# LED_rev3.net
KiCad netlist of a schematic drawn in EAGLE
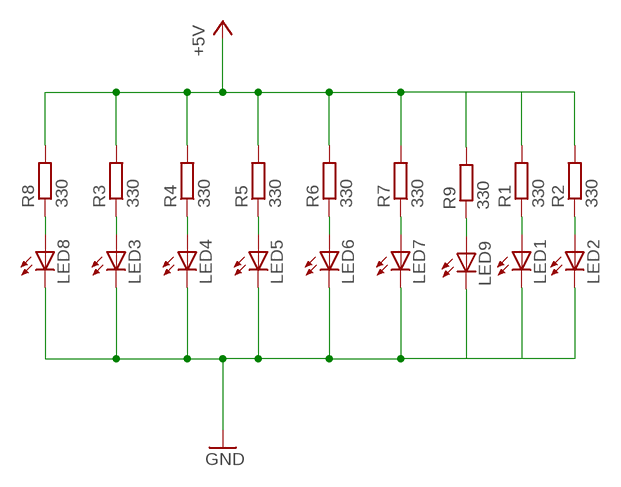
[diagram p0: schematic, sheet 1]

(export (version "E")
  (design (tool "Eeschema 10.0.6"))
  (components
    (comp (ref "LED1")
      (value "LEDCHIPLED_0603")
      (footprint "eagle-import:CHIPLED_0603")
      (libsource (lib "eagle-import") (part "LEDCHIPLED_0603"))
    )
    (comp (ref "LED2")
      (value "LEDCHIPLED_0603")
      (footprint "eagle-import:CHIPLED_0603")
      (libsource (lib "eagle-import") (part "LEDCHIPLED_0603"))
    )
    (comp (ref "LED3")
      (value "LEDCHIPLED_0603")
      (footprint "eagle-import:CHIPLED_0603")
      (libsource (lib "eagle-import") (part "LEDCHIPLED_0603"))
    )
    (comp (ref "LED4")
      (value "LEDCHIPLED_0603")
      (footprint "eagle-import:CHIPLED_0603")
      (libsource (lib "eagle-import") (part "LEDCHIPLED_0603"))
    )
    (comp (ref "LED5")
      (value "LEDCHIPLED_0603")
      (footprint "eagle-import:CHIPLED_0603")
      (libsource (lib "eagle-import") (part "LEDCHIPLED_0603"))
    )
    (comp (ref "LED6")
      (value "LEDCHIPLED_0603")
      (footprint "eagle-import:CHIPLED_0603")
      (libsource (lib "eagle-import") (part "LEDCHIPLED_0603"))
    )
    (comp (ref "LED7")
      (value "LEDCHIPLED_0603")
      (footprint "eagle-import:CHIPLED_0603")
      (libsource (lib "eagle-import") (part "LEDCHIPLED_0603"))
    )
    (comp (ref "LED8")
      (value "LEDCHIPLED_0603")
      (footprint "eagle-import:CHIPLED_0603")
      (libsource (lib "eagle-import") (part "LEDCHIPLED_0603"))
    )
    (comp (ref "LED9")
      (value "LEDCHIPLED_0603")
      (footprint "eagle-import:CHIPLED_0603")
      (libsource (lib "eagle-import") (part "LEDCHIPLED_0603"))
    )
    (comp (ref "R1")
      (value "330")
      (footprint "eagle-import:R0603")
      (libsource (lib "eagle-import") (part "R-EU_R0603"))
    )
    (comp (ref "R2")
      (value "330")
      (footprint "eagle-import:R0603")
      (libsource (lib "eagle-import") (part "R-EU_R0603"))
    )
    (comp (ref "R3")
      (value "330")
      (footprint "eagle-import:R0603")
      (libsource (lib "eagle-import") (part "R-EU_R0603"))
    )
    (comp (ref "R4")
      (value "330")
      (footprint "eagle-import:R0603")
      (libsource (lib "eagle-import") (part "R-EU_R0603"))
    )
    (comp (ref "R5")
      (value "330")
      (footprint "eagle-import:R0603")
      (libsource (lib "eagle-import") (part "R-EU_R0603"))
    )
    (comp (ref "R6")
      (value "330")
      (footprint "eagle-import:R0603")
      (libsource (lib "eagle-import") (part "R-EU_R0603"))
    )
    (comp (ref "R7")
      (value "330")
      (footprint "eagle-import:R0603")
      (libsource (lib "eagle-import") (part "R-EU_R0603"))
    )
    (comp (ref "R8")
      (value "330")
      (footprint "eagle-import:R0603")
      (libsource (lib "eagle-import") (part "R-EU_R0603"))
    )
    (comp (ref "R9")
      (value "330")
      (footprint "eagle-import:R0603")
      (libsource (lib "eagle-import") (part "R-EU_R0603"))
    )
  )
  (nets
    (net (code "1") (name "+5V") (class "Default")
      (node (ref "R1") (pin "2") (pinfunction "2_2") (pintype "passive"))
      (node (ref "R2") (pin "2") (pinfunction "2_2") (pintype "passive"))
      (node (ref "R3") (pin "2") (pinfunction "2_2") (pintype "passive"))
      (node (ref "R4") (pin "2") (pinfunction "2_2") (pintype "passive"))
      (node (ref "R5") (pin "2") (pinfunction "2_2") (pintype "passive"))
      (node (ref "R6") (pin "2") (pinfunction "2_2") (pintype "passive"))
      (node (ref "R7") (pin "2") (pinfunction "2_2") (pintype "passive"))
      (node (ref "R8") (pin "2") (pinfunction "2_2") (pintype "passive"))
      (node (ref "R9") (pin "2") (pinfunction "2_2") (pintype "passive"))
    )
    (net (code "2") (name "GND") (class "Default")
      (node (ref "LED1") (pin "C") (pinfunction "C_C") (pintype "passive"))
      (node (ref "LED2") (pin "C") (pinfunction "C_C") (pintype "passive"))
      (node (ref "LED3") (pin "C") (pinfunction "C_C") (pintype "passive"))
      (node (ref "LED4") (pin "C") (pinfunction "C_C") (pintype "passive"))
      (node (ref "LED5") (pin "C") (pinfunction "C_C") (pintype "passive"))
      (node (ref "LED6") (pin "C") (pinfunction "C_C") (pintype "passive"))
      (node (ref "LED7") (pin "C") (pinfunction "C_C") (pintype "passive"))
      (node (ref "LED8") (pin "C") (pinfunction "C_C") (pintype "passive"))
      (node (ref "LED9") (pin "C") (pinfunction "C_C") (pintype "passive"))
    )
    (net (code "3") (name "Net-(LED1-PadA)") (class "Default")
      (node (ref "LED1") (pin "A") (pinfunction "A_A") (pintype "passive"))
      (node (ref "R1") (pin "1") (pinfunction "1_1") (pintype "passive"))
    )
    (net (code "4") (name "Net-(LED2-PadA)") (class "Default")
      (node (ref "LED2") (pin "A") (pinfunction "A_A") (pintype "passive"))
      (node (ref "R2") (pin "1") (pinfunction "1_1") (pintype "passive"))
    )
    (net (code "5") (name "Net-(LED3-PadA)") (class "Default")
      (node (ref "LED3") (pin "A") (pinfunction "A_A") (pintype "passive"))
      (node (ref "R3") (pin "1") (pinfunction "1_1") (pintype "passive"))
    )
    (net (code "6") (name "Net-(LED4-PadA)") (class "Default")
      (node (ref "LED4") (pin "A") (pinfunction "A_A") (pintype "passive"))
      (node (ref "R4") (pin "1") (pinfunction "1_1") (pintype "passive"))
    )
    (net (code "7") (name "Net-(LED5-PadA)") (class "Default")
      (node (ref "LED5") (pin "A") (pinfunction "A_A") (pintype "passive"))
      (node (ref "R5") (pin "1") (pinfunction "1_1") (pintype "passive"))
    )
    (net (code "8") (name "Net-(LED6-PadA)") (class "Default")
      (node (ref "LED6") (pin "A") (pinfunction "A_A") (pintype "passive"))
      (node (ref "R6") (pin "1") (pinfunction "1_1") (pintype "passive"))
    )
    (net (code "9") (name "Net-(LED7-PadA)") (class "Default")
      (node (ref "LED7") (pin "A") (pinfunction "A_A") (pintype "passive"))
      (node (ref "R7") (pin "1") (pinfunction "1_1") (pintype "passive"))
    )
    (net (code "10") (name "Net-(LED8-PadA)") (class "Default")
      (node (ref "LED8") (pin "A") (pinfunction "A_A") (pintype "passive"))
      (node (ref "R8") (pin "1") (pinfunction "1_1") (pintype "passive"))
    )
    (net (code "11") (name "Net-(LED9-PadA)") (class "Default")
      (node (ref "LED9") (pin "A") (pinfunction "A_A") (pintype "passive"))
      (node (ref "R9") (pin "1") (pinfunction "1_1") (pintype "passive"))
    )
  )
)
